# stepper1.net
KiCad netlist of a schematic drawn in EAGLE
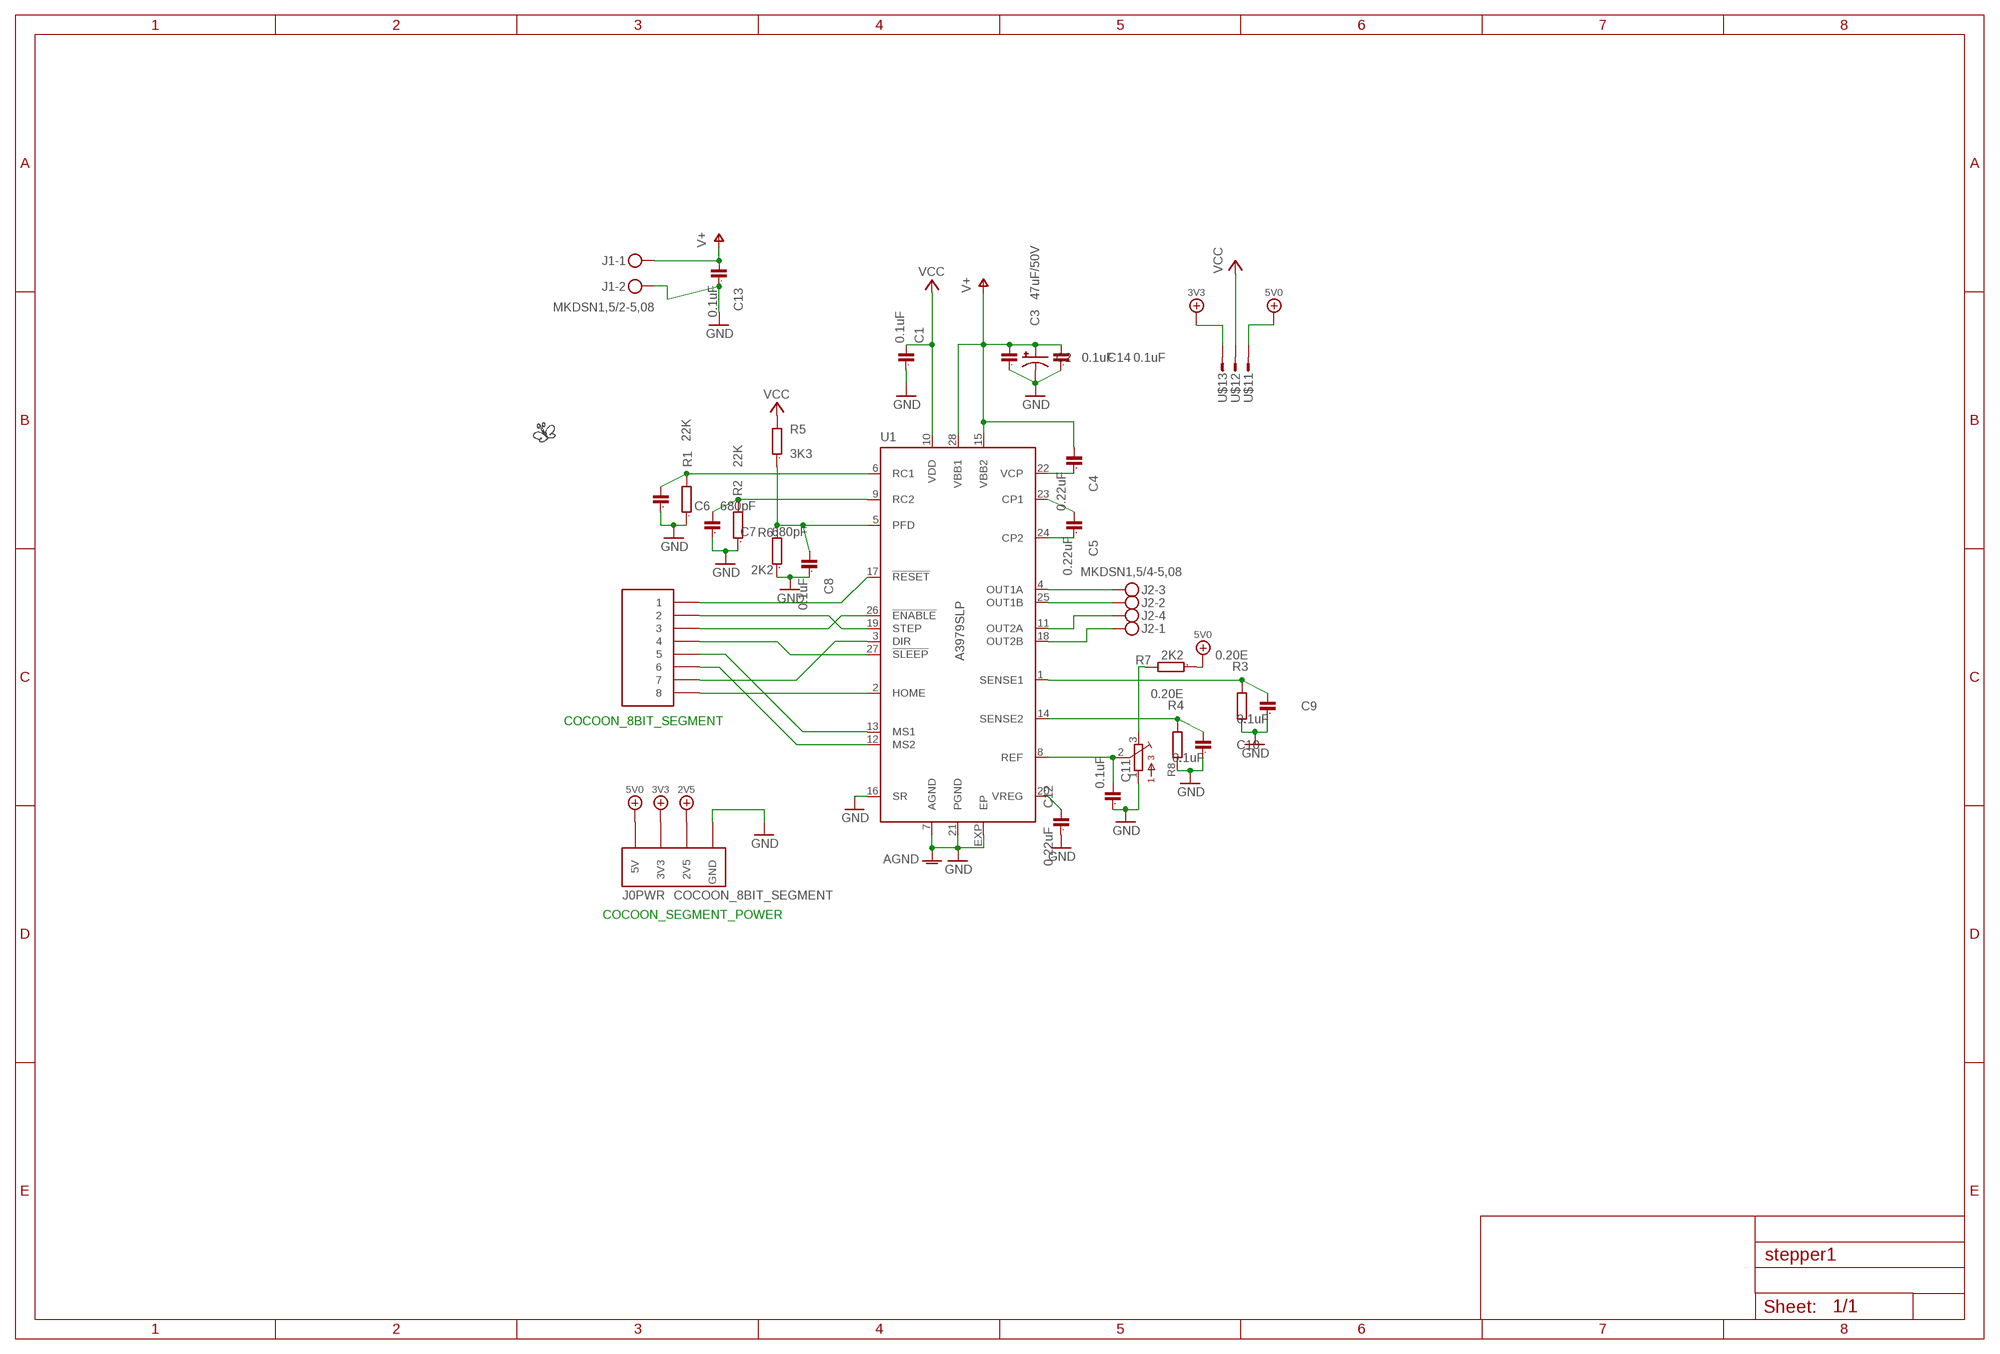
[diagram p0: schematic, sheet 1]

(export (version "E")
  (design (tool "Eeschema 10.0.6"))
  (components
    (comp (ref "C1")
      (value "0.1uF")
      (footprint "eagle-import:0603")
      (libsource (lib "eagle-import") (part "C0603"))
    )
    (comp (ref "C2")
      (value "0.1uF")
      (footprint "eagle-import:0805")
      (libsource (lib "eagle-import") (part "C0805"))
    )
    (comp (ref "C3")
      (value "47uF/50V")
      (footprint "eagle-import:E2,5-7")
      (libsource (lib "eagle-import") (part "CPOL-USE2.5-7"))
    )
    (comp (ref "C4")
      (value "0.22uF")
      (footprint "eagle-import:0805")
      (libsource (lib "eagle-import") (part "C0805"))
    )
    (comp (ref "C5")
      (value "0.22uF")
      (footprint "eagle-import:0805")
      (libsource (lib "eagle-import") (part "C0805"))
    )
    (comp (ref "C6")
      (value "680pF")
      (footprint "eagle-import:0603")
      (libsource (lib "eagle-import") (part "C0603"))
    )
    (comp (ref "C7")
      (value "680pF")
      (footprint "eagle-import:0603")
      (libsource (lib "eagle-import") (part "C0603"))
    )
    (comp (ref "C8")
      (value "0.1uF")
      (footprint "eagle-import:0603")
      (libsource (lib "eagle-import") (part "C0603"))
    )
    (comp (ref "C9")
      (value "0.1uF")
      (footprint "eagle-import:0805")
      (libsource (lib "eagle-import") (part "C0805"))
    )
    (comp (ref "C10")
      (value "0.1uF")
      (footprint "eagle-import:0805")
      (libsource (lib "eagle-import") (part "C0805"))
    )
    (comp (ref "C11")
      (value "0.1uF")
      (footprint "eagle-import:0603")
      (libsource (lib "eagle-import") (part "C0603"))
    )
    (comp (ref "C12")
      (value "0.22uF")
      (footprint "eagle-import:0805")
      (libsource (lib "eagle-import") (part "C0805"))
    )
    (comp (ref "C13")
      (value "0.1uF")
      (footprint "eagle-import:0805")
      (libsource (lib "eagle-import") (part "C0805"))
    )
    (comp (ref "C14")
      (value "0.1uF")
      (footprint "eagle-import:0805")
      (libsource (lib "eagle-import") (part "C0805"))
    )
    (comp (ref "J0")
      (value "COCOON_8BIT_SEGMENT")
      (footprint "eagle-import:COCOON_8BIT_SEGMENT")
      (libsource (lib "eagle-import") (part "COCOON_8BIT_SEGMENT"))
    )
    (comp (ref "J1")
      (value "MKDSN1,5/2-5,08")
      (footprint "eagle-import:MKDSN1,5_2-5,08")
      (libsource (lib "eagle-import") (part "MKDSN1,5/2-5,08"))
    )
    (comp (ref "J2")
      (value "MKDSN1,5/4-5,08")
      (footprint "eagle-import:MKDSN1,5_4-5,08")
      (libsource (lib "eagle-import") (part "MKDSN1,5/4-5,08"))
    )
    (comp (ref "LOGO1")
      (value "BUTTERFLY_LOGO")
      (footprint "eagle-import:BUTTERFLY_LOGO")
      (libsource (lib "eagle-import") (part "BUTTERFLY_LOGO"))
    )
    (comp (ref "R1")
      (value "22K")
      (footprint "eagle-import:0603")
      (libsource (lib "eagle-import") (part "R0603"))
    )
    (comp (ref "R2")
      (value "22K")
      (footprint "eagle-import:0603")
      (libsource (lib "eagle-import") (part "R0603"))
    )
    (comp (ref "R3")
      (value "0.20E")
      (footprint "eagle-import:2512")
      (libsource (lib "eagle-import") (part "R2512"))
    )
    (comp (ref "R4")
      (value "0.20E")
      (footprint "eagle-import:2512")
      (libsource (lib "eagle-import") (part "R2512"))
    )
    (comp (ref "R5")
      (value "3K3")
      (footprint "eagle-import:0603")
      (libsource (lib "eagle-import") (part "R0603"))
    )
    (comp (ref "R6")
      (value "2K2")
      (footprint "eagle-import:0603")
      (libsource (lib "eagle-import") (part "R0603"))
    )
    (comp (ref "R7")
      (value "2K2")
      (footprint "eagle-import:0603")
      (libsource (lib "eagle-import") (part "R0603"))
    )
    (comp (ref "R8")
      (value "3386-P")
      (footprint "eagle-import:3386P")
      (libsource (lib "eagle-import") (part "3386-P"))
    )
    (comp (ref "U$1")
      (value "JPS3X1")
      (footprint "eagle-import:JP3X1")
      (libsource (lib "eagle-import") (part "JPS3X1"))
    )
    (comp (ref "U1")
      (value "A3979SLP")
      (footprint "eagle-import:TSSOP28")
      (libsource (lib "eagle-import") (part "A3979SLP"))
    )
  )
  (nets
    (net (code "1") (name "2V5") (class "Default")
      (node (ref "J0") (pin "2V5") (pinfunction "2V5_2V5") (pintype "power_in"))
    )
    (net (code "2") (name "3V3") (class "Default")
      (node (ref "J0") (pin "3V3") (pinfunction "3V3_3V3") (pintype "power_in"))
      (node (ref "U$1") (pin "3") (pinfunction "S_3") (pintype "passive"))
    )
    (net (code "3") (name "5V0") (class "Default")
      (node (ref "J0") (pin "5V") (pinfunction "5V_5V") (pintype "power_in"))
      (node (ref "R7") (pin "1") (pinfunction "1_1") (pintype "passive"))
      (node (ref "U$1") (pin "1") (pinfunction "S_1") (pintype "passive"))
    )
    (net (code "4") (name "AGND") (class "Default")
      (node (ref "C1") (pin "1") (pinfunction "1_1") (pintype "passive"))
      (node (ref "C10") (pin "1") (pinfunction "1_1") (pintype "passive"))
      (node (ref "C11") (pin "1") (pinfunction "1_1") (pintype "passive"))
      (node (ref "C12") (pin "1") (pinfunction "1_1") (pintype "passive"))
      (node (ref "C13") (pin "1") (pinfunction "1_1") (pintype "passive"))
      (node (ref "C14") (pin "1") (pinfunction "1_1") (pintype "passive"))
      (node (ref "C2") (pin "1") (pinfunction "1_1") (pintype "passive"))
      (node (ref "C3") (pin "-") (pinfunction "-_-") (pintype "passive"))
      (node (ref "C6") (pin "1") (pinfunction "1_1") (pintype "passive"))
      (node (ref "C7") (pin "1") (pinfunction "1_1") (pintype "passive"))
      (node (ref "C8") (pin "1") (pinfunction "1_1") (pintype "passive"))
      (node (ref "C9") (pin "1") (pinfunction "1_1") (pintype "passive"))
      (node (ref "J0") (pin "GND") (pinfunction "GND_GND") (pintype "power_in"))
      (node (ref "J1") (pin "2") (pinfunction "KL_2") (pintype "passive"))
      (node (ref "R1") (pin "1") (pinfunction "1_1") (pintype "passive"))
      (node (ref "R2") (pin "1") (pinfunction "1_1") (pintype "passive"))
      (node (ref "R3") (pin "1") (pinfunction "1_1") (pintype "passive"))
      (node (ref "R4") (pin "1") (pinfunction "1_1") (pintype "passive"))
      (node (ref "R6") (pin "1") (pinfunction "1_1") (pintype "passive"))
      (node (ref "R8") (pin "1") (pinfunction "1_1") (pintype "passive"))
      (node (ref "U1") (pin "16") (pinfunction "SR_16") (pintype "input"))
      (node (ref "U1") (pin "21") (pinfunction "PGND_21") (pintype "power_in"))
      (node (ref "U1") (pin "7") (pinfunction "AGND_7") (pintype "power_in"))
      (node (ref "U1") (pin "EXP") (pinfunction "EP_EXP") (pintype "power_in"))
    )
    (net (code "5") (name "Net-(J2A-KL)") (class "Default")
      (node (ref "J2") (pin "1") (pinfunction "KL_1") (pintype "passive"))
      (node (ref "U1") (pin "18") (pinfunction "OUT2B_18") (pintype "output"))
    )
    (net (code "6") (name "Net-(J2B-KL)") (class "Default")
      (node (ref "J2") (pin "2") (pinfunction "KL_2") (pintype "passive"))
      (node (ref "U1") (pin "25") (pinfunction "OUT1B_25") (pintype "output"))
    )
    (net (code "7") (name "Net-(J2C-KL)") (class "Default")
      (node (ref "J2") (pin "3") (pinfunction "KL_3") (pintype "passive"))
      (node (ref "U1") (pin "4") (pinfunction "OUT1A_4") (pintype "output"))
    )
    (net (code "8") (name "Net-(J2D-KL)") (class "Default")
      (node (ref "J2") (pin "4") (pinfunction "KL_4") (pintype "passive"))
      (node (ref "U1") (pin "11") (pinfunction "OUT2A_11") (pintype "output"))
    )
    (net (code "9") (name "Net-(R7-Pad2)") (class "Default")
      (node (ref "R7") (pin "2") (pinfunction "2_2") (pintype "passive"))
      (node (ref "R8") (pin "3") (pinfunction "3_3") (pintype "passive"))
    )
    (net (code "10") (name "Net-(U1-CP1)") (class "Default")
      (node (ref "C5") (pin "2") (pinfunction "2_2") (pintype "passive"))
      (node (ref "U1") (pin "23") (pinfunction "CP1_23") (pintype "input"))
    )
    (net (code "11") (name "Net-(U1-CP2)") (class "Default")
      (node (ref "C5") (pin "1") (pinfunction "1_1") (pintype "passive"))
      (node (ref "U1") (pin "24") (pinfunction "CP2_24") (pintype "input"))
    )
    (net (code "12") (name "Net-(U1-DIR)") (class "Default")
      (node (ref "J0") (pin "7") (pinfunction "7_7") (pintype "bidirectional"))
      (node (ref "U1") (pin "3") (pinfunction "DIR_3") (pintype "input"))
    )
    (net (code "13") (name "Net-(U1-HOME)") (class "Default")
      (node (ref "J0") (pin "8") (pinfunction "8_8") (pintype "bidirectional"))
      (node (ref "U1") (pin "2") (pinfunction "HOME_2") (pintype "input"))
    )
    (net (code "14") (name "Net-(U1-MS1)") (class "Default")
      (node (ref "J0") (pin "5") (pinfunction "5_5") (pintype "bidirectional"))
      (node (ref "U1") (pin "13") (pinfunction "MS1_13") (pintype "input"))
    )
    (net (code "15") (name "Net-(U1-MS2)") (class "Default")
      (node (ref "J0") (pin "6") (pinfunction "6_6") (pintype "bidirectional"))
      (node (ref "U1") (pin "12") (pinfunction "MS2_12") (pintype "input"))
    )
    (net (code "16") (name "Net-(U1-PFD)") (class "Default")
      (node (ref "C8") (pin "2") (pinfunction "2_2") (pintype "passive"))
      (node (ref "R5") (pin "1") (pinfunction "1_1") (pintype "passive"))
      (node (ref "R6") (pin "2") (pinfunction "2_2") (pintype "passive"))
      (node (ref "U1") (pin "5") (pinfunction "PFD_5") (pintype "input"))
    )
    (net (code "17") (name "Net-(U1-RC1)") (class "Default")
      (node (ref "C6") (pin "2") (pinfunction "2_2") (pintype "passive"))
      (node (ref "R1") (pin "2") (pinfunction "2_2") (pintype "passive"))
      (node (ref "U1") (pin "6") (pinfunction "RC1_6") (pintype "input"))
    )
    (net (code "18") (name "Net-(U1-RC2)") (class "Default")
      (node (ref "C7") (pin "2") (pinfunction "2_2") (pintype "passive"))
      (node (ref "R2") (pin "2") (pinfunction "2_2") (pintype "passive"))
      (node (ref "U1") (pin "9") (pinfunction "RC2_9") (pintype "input"))
    )
    (net (code "19") (name "Net-(U1-REF)") (class "Default")
      (node (ref "C11") (pin "2") (pinfunction "2_2") (pintype "passive"))
      (node (ref "R8") (pin "2") (pinfunction "2_2") (pintype "passive"))
      (node (ref "U1") (pin "8") (pinfunction "REF_8") (pintype "input"))
    )
    (net (code "20") (name "Net-(U1-SENSE1)") (class "Default")
      (node (ref "C9") (pin "2") (pinfunction "2_2") (pintype "passive"))
      (node (ref "R3") (pin "2") (pinfunction "2_2") (pintype "passive"))
      (node (ref "U1") (pin "1") (pinfunction "SENSE1_1") (pintype "input"))
    )
    (net (code "21") (name "Net-(U1-SENSE2)") (class "Default")
      (node (ref "C10") (pin "2") (pinfunction "2_2") (pintype "passive"))
      (node (ref "R4") (pin "2") (pinfunction "2_2") (pintype "passive"))
      (node (ref "U1") (pin "14") (pinfunction "SENSE2_14") (pintype "input"))
    )
    (net (code "22") (name "Net-(U1-STEP)") (class "Default")
      (node (ref "J0") (pin "2") (pinfunction "2_2") (pintype "bidirectional"))
      (node (ref "U1") (pin "19") (pinfunction "STEP_19") (pintype "input"))
    )
    (net (code "23") (name "Net-(U1-VCP)") (class "Default")
      (node (ref "C4") (pin "1") (pinfunction "1_1") (pintype "passive"))
      (node (ref "U1") (pin "22") (pinfunction "VCP_22") (pintype "input"))
    )
    (net (code "24") (name "Net-(U1-VREG)") (class "Default")
      (node (ref "C12") (pin "2") (pinfunction "2_2") (pintype "passive"))
      (node (ref "U1") (pin "20") (pinfunction "VREG_20") (pintype "input"))
    )
    (net (code "25") (name "Net-(U1-~{ENABLE})") (class "Default")
      (node (ref "J0") (pin "3") (pinfunction "3_3") (pintype "bidirectional"))
      (node (ref "U1") (pin "26") (pinfunction "~{ENABLE}_26") (pintype "input"))
    )
    (net (code "26") (name "Net-(U1-~{RESET})") (class "Default")
      (node (ref "J0") (pin "1") (pinfunction "1_1") (pintype "bidirectional"))
      (node (ref "U1") (pin "17") (pinfunction "~{RESET}_17") (pintype "input"))
    )
    (net (code "27") (name "Net-(U1-~{SLEEP})") (class "Default")
      (node (ref "J0") (pin "4") (pinfunction "4_4") (pintype "bidirectional"))
      (node (ref "U1") (pin "27") (pinfunction "~{SLEEP}_27") (pintype "input"))
    )
    (net (code "28") (name "V+") (class "Default")
      (node (ref "C13") (pin "2") (pinfunction "2_2") (pintype "passive"))
      (node (ref "C14") (pin "2") (pinfunction "2_2") (pintype "passive"))
      (node (ref "C2") (pin "2") (pinfunction "2_2") (pintype "passive"))
      (node (ref "C3") (pin "+") (pinfunction "+_+") (pintype "passive"))
      (node (ref "C4") (pin "2") (pinfunction "2_2") (pintype "passive"))
      (node (ref "J1") (pin "1") (pinfunction "KL_1") (pintype "passive"))
      (node (ref "U1") (pin "15") (pinfunction "VBB2_15") (pintype "input"))
      (node (ref "U1") (pin "28") (pinfunction "VBB1_28") (pintype "input"))
    )
    (net (code "29") (name "VCC") (class "Default")
      (node (ref "C1") (pin "2") (pinfunction "2_2") (pintype "passive"))
      (node (ref "R5") (pin "2") (pinfunction "2_2") (pintype "passive"))
      (node (ref "U$1") (pin "2") (pinfunction "S_2") (pintype "passive"))
      (node (ref "U1") (pin "10") (pinfunction "VDD_10") (pintype "power_in"))
    )
  )
)
